# Pluvion_2_-_Rev_G.net
KiCad netlist of a schematic drawn in EAGLE
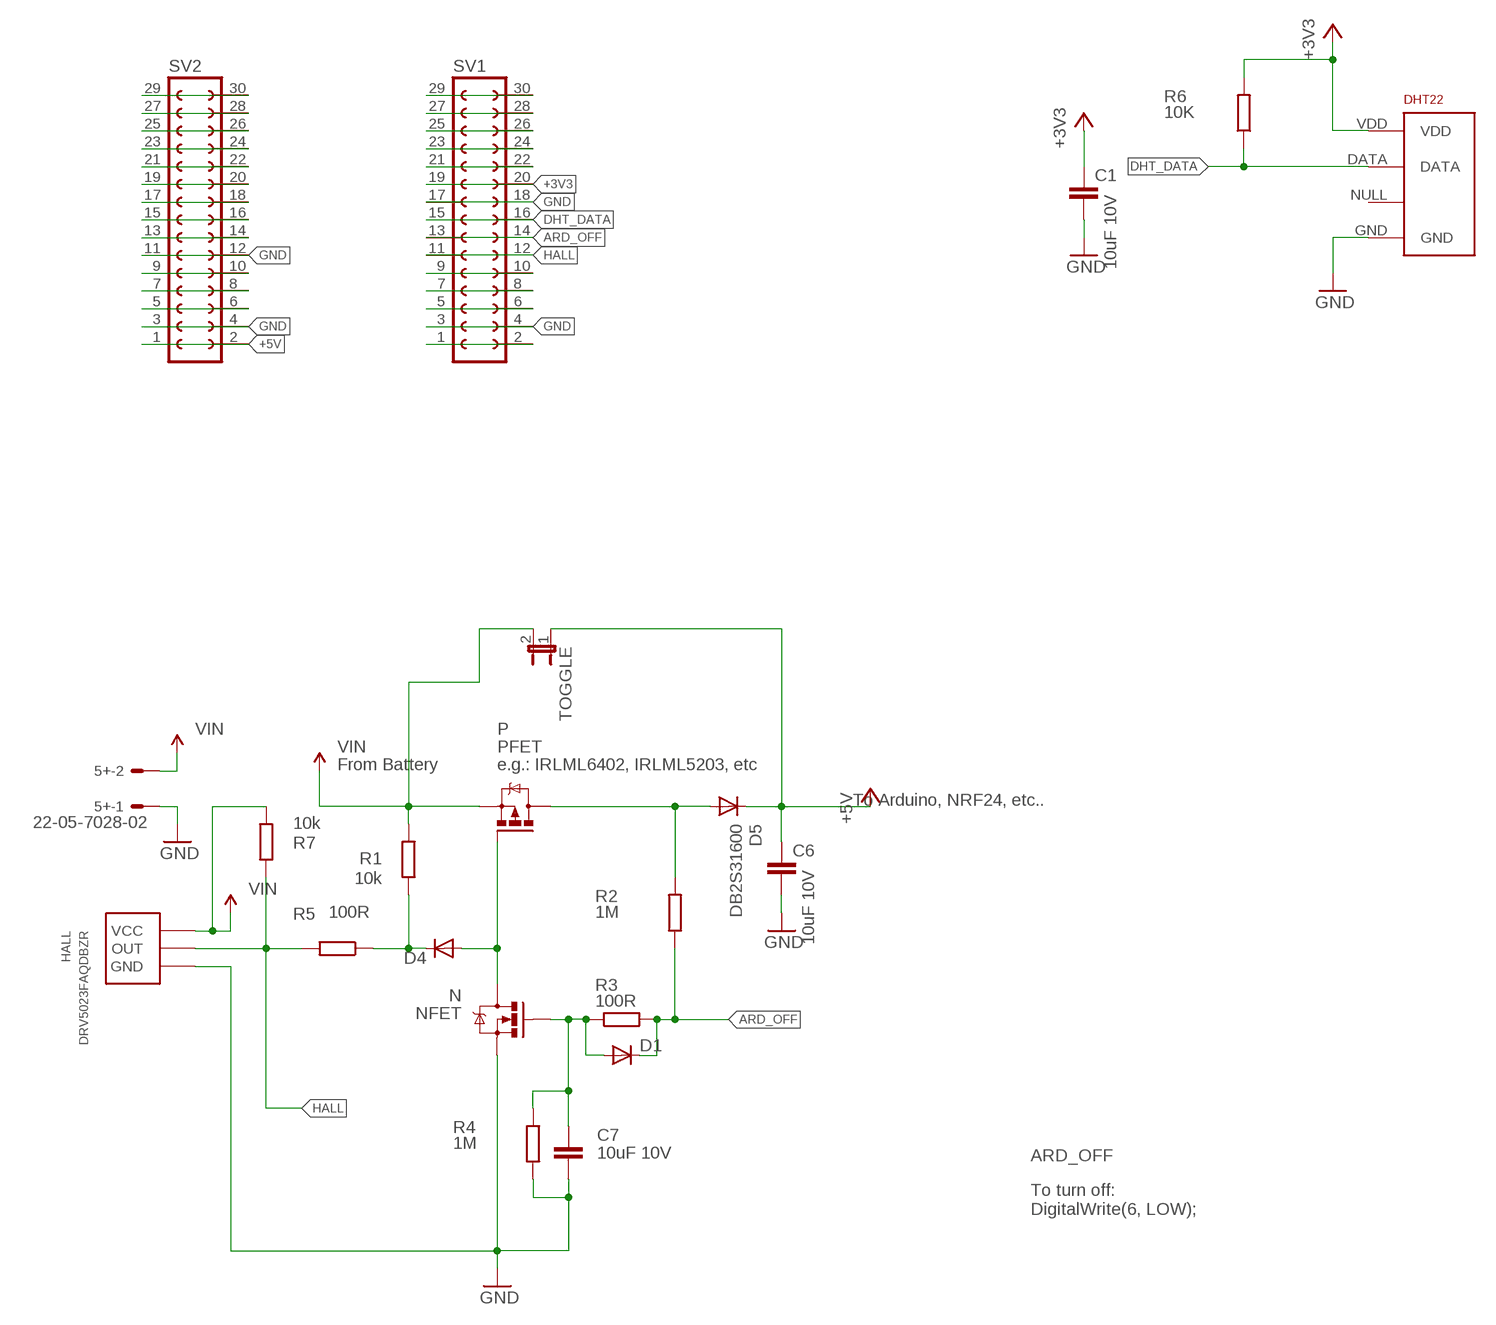
[diagram p0: schematic, sheet 1]

(export (version "E")
  (design (tool "Eeschema 10.0.6"))
  (components
    (comp (ref "5+")
      (value "22-05-7028-02")
      (footprint "eagle-import:7395-02")
      (libsource (lib "eagle-import") (part "22-?-0205-7028"))
    )
    (comp (ref "C1")
      (value "10uF 10V")
      (footprint "eagle-import:C0805")
      (libsource (lib "eagle-import") (part "C-EUC0805"))
    )
    (comp (ref "C6")
      (value "10uF 10V")
      (footprint "eagle-import:C0805")
      (libsource (lib "eagle-import") (part "C-EUC0805"))
    )
    (comp (ref "C7")
      (value "10uF 10V")
      (footprint "eagle-import:C0805")
      (libsource (lib "eagle-import") (part "C-EUC0805"))
    )
    (comp (ref "D1")
      (value "DIODESOD")
      (footprint "eagle-import:SOD-323")
      (libsource (lib "eagle-import") (part "DIODESOD"))
    )
    (comp (ref "D4")
      (value "DIODESOD")
      (footprint "eagle-import:SOD-323")
      (libsource (lib "eagle-import") (part "DIODESOD"))
    )
    (comp (ref "D5")
      (value "DB2S31600")
      (footprint "eagle-import:SMA-DIODE")
      (libsource (lib "eagle-import") (part "DIODESMA"))
    )
    (comp (ref "DHT22")
      (value "RHT03_DHT-22_AM2302RA")
      (footprint "eagle-import:RHT03_DHT-22_RA")
      (libsource (lib "eagle-import") (part "RHT03_DHT-22_AM2302RA"))
    )
    (comp (ref "HALL")
      (value "DRV5023FAQDBZR")
      (footprint "eagle-import:SOT23")
      (libsource (lib "eagle-import") (part "DRV5023FAQDBZR"))
    )
    (comp (ref "N")
      (value "NFET")
      (footprint "eagle-import:SOT23")
      (libsource (lib "eagle-import") (part "MOSFET-NCHANNELBSS123LT1G"))
    )
    (comp (ref "P")
      (value "PFET")
      (footprint "eagle-import:MICRO3")
      (libsource (lib "eagle-import") (part "IRLML5203"))
    )
    (comp (ref "R1")
      (value "10k")
      (footprint "eagle-import:R0805")
      (libsource (lib "eagle-import") (part "R-EU_R0805"))
    )
    (comp (ref "R2")
      (value "1M")
      (footprint "eagle-import:R0805")
      (libsource (lib "eagle-import") (part "R-EU_R0805"))
    )
    (comp (ref "R3")
      (value "100R")
      (footprint "eagle-import:R0805")
      (libsource (lib "eagle-import") (part "R-EU_R0805"))
    )
    (comp (ref "R4")
      (value "1M")
      (footprint "eagle-import:R0805")
      (libsource (lib "eagle-import") (part "R-EU_R0805"))
    )
    (comp (ref "R5")
      (value "100R")
      (footprint "eagle-import:R0805")
      (libsource (lib "eagle-import") (part "R-EU_R0805"))
    )
    (comp (ref "R6")
      (value "10K")
      (footprint "eagle-import:R0805")
      (libsource (lib "eagle-import") (part "R-EU_R0805"))
    )
    (comp (ref "R7")
      (value "10k")
      (footprint "eagle-import:R0805")
      (libsource (lib "eagle-import") (part "R-EU_R0805"))
    )
    (comp (ref "SV1")
      (value "FE15-2")
      (footprint "eagle-import:FE15-2")
      (libsource (lib "eagle-import") (part "FE15-2"))
    )
    (comp (ref "SV2")
      (value "FE15-2")
      (footprint "eagle-import:FE15-2")
      (libsource (lib "eagle-import") (part "FE15-2"))
    )
    (comp (ref "TOGGLE")
      (value "JUMPER-2PTH")
      (footprint "eagle-import:1X02")
      (libsource (lib "eagle-import") (part "JUMPER-2PTH"))
    )
  )
  (nets
    (net (code "1") (name "+3V3") (class "Default")
      (node (ref "C1") (pin "1") (pinfunction "1_1") (pintype "passive"))
      (node (ref "DHT22") (pin "VDD") (pinfunction "VDD_VDD") (pintype "power_in"))
      (node (ref "R6") (pin "2") (pinfunction "2_2") (pintype "passive"))
      (node (ref "SV1") (pin "19") (pinfunction "19_19") (pintype "passive"))
      (node (ref "SV1") (pin "20") (pinfunction "20_20") (pintype "passive"))
    )
    (net (code "2") (name "+5V") (class "Default")
      (node (ref "C6") (pin "1") (pinfunction "1_1") (pintype "passive"))
      (node (ref "D5") (pin "C") (pinfunction "C_C") (pintype "passive"))
      (node (ref "SV2") (pin "1") (pinfunction "1_1") (pintype "passive"))
      (node (ref "SV2") (pin "2") (pinfunction "2_2") (pintype "passive"))
      (node (ref "TOGGLE") (pin "1") (pinfunction "1_1") (pintype "passive"))
    )
    (net (code "3") (name "ARD_OFF") (class "Default")
      (node (ref "D1") (pin "1") (pinfunction "C_1") (pintype "passive"))
      (node (ref "R2") (pin "1") (pinfunction "1_1") (pintype "passive"))
      (node (ref "R3") (pin "2") (pinfunction "2_2") (pintype "passive"))
      (node (ref "SV1") (pin "13") (pinfunction "13_13") (pintype "passive"))
      (node (ref "SV1") (pin "14") (pinfunction "14_14") (pintype "passive"))
    )
    (net (code "4") (name "DHT_DATA") (class "Default")
      (node (ref "DHT22") (pin "DATA") (pinfunction "DATA_DATA") (pintype "bidirectional"))
      (node (ref "R6") (pin "1") (pinfunction "1_1") (pintype "passive"))
      (node (ref "SV1") (pin "15") (pinfunction "15_15") (pintype "passive"))
      (node (ref "SV1") (pin "16") (pinfunction "16_16") (pintype "passive"))
    )
    (net (code "5") (name "GND") (class "Default")
      (node (ref "5+") (pin "1") (pinfunction "S_1") (pintype "passive"))
      (node (ref "C1") (pin "2") (pinfunction "2_2") (pintype "passive"))
      (node (ref "C6") (pin "2") (pinfunction "2_2") (pintype "passive"))
      (node (ref "C7") (pin "2") (pinfunction "2_2") (pintype "passive"))
      (node (ref "DHT22") (pin "GND") (pinfunction "GND_GND") (pintype "power_in"))
      (node (ref "HALL") (pin "3") (pinfunction "GND_3") (pintype "bidirectional"))
      (node (ref "N") (pin "2") (pinfunction "S_2") (pintype "passive"))
      (node (ref "R4") (pin "1") (pinfunction "1_1") (pintype "passive"))
      (node (ref "SV1") (pin "17") (pinfunction "17_17") (pintype "passive"))
      (node (ref "SV1") (pin "18") (pinfunction "18_18") (pintype "passive"))
      (node (ref "SV1") (pin "3") (pinfunction "3_3") (pintype "passive"))
      (node (ref "SV1") (pin "4") (pinfunction "4_4") (pintype "passive"))
      (node (ref "SV2") (pin "11") (pinfunction "11_11") (pintype "passive"))
      (node (ref "SV2") (pin "12") (pinfunction "12_12") (pintype "passive"))
      (node (ref "SV2") (pin "3") (pinfunction "3_3") (pintype "passive"))
      (node (ref "SV2") (pin "4") (pinfunction "4_4") (pintype "passive"))
    )
    (net (code "6") (name "HALL") (class "Default")
      (node (ref "HALL") (pin "2") (pinfunction "OUT_2") (pintype "bidirectional"))
      (node (ref "R5") (pin "2") (pinfunction "2_2") (pintype "passive"))
      (node (ref "R7") (pin "2") (pinfunction "2_2") (pintype "passive"))
      (node (ref "SV1") (pin "11") (pinfunction "11_11") (pintype "passive"))
      (node (ref "SV1") (pin "12") (pinfunction "12_12") (pintype "passive"))
    )
    (net (code "7") (name "Net-(D1-A)") (class "Default")
      (node (ref "C7") (pin "1") (pinfunction "1_1") (pintype "passive"))
      (node (ref "D1") (pin "2") (pinfunction "A_2") (pintype "passive"))
      (node (ref "N") (pin "1") (pinfunction "G_1") (pintype "passive"))
      (node (ref "R3") (pin "1") (pinfunction "1_1") (pintype "passive"))
      (node (ref "R4") (pin "2") (pinfunction "2_2") (pintype "passive"))
    )
    (net (code "8") (name "Net-(D4-A)") (class "Default")
      (node (ref "D4") (pin "2") (pinfunction "A_2") (pintype "passive"))
      (node (ref "N") (pin "3") (pinfunction "D_3") (pintype "passive"))
      (node (ref "P") (pin "1") (pinfunction "G_1") (pintype "passive"))
    )
    (net (code "9") (name "Net-(D4-C)") (class "Default")
      (node (ref "D4") (pin "1") (pinfunction "C_1") (pintype "passive"))
      (node (ref "R1") (pin "1") (pinfunction "1_1") (pintype "passive"))
      (node (ref "R5") (pin "1") (pinfunction "1_1") (pintype "passive"))
    )
    (net (code "10") (name "Net-(P-D)") (class "Default")
      (node (ref "D5") (pin "A") (pinfunction "A_A") (pintype "passive"))
      (node (ref "P") (pin "3") (pinfunction "D_3") (pintype "passive"))
      (node (ref "R2") (pin "2") (pinfunction "2_2") (pintype "passive"))
    )
    (net (code "11") (name "Net-(SV1-Pad1)") (class "Default")
      (node (ref "SV1") (pin "1") (pinfunction "1_1") (pintype "passive"))
      (node (ref "SV1") (pin "2") (pinfunction "2_2") (pintype "passive"))
    )
    (net (code "12") (name "Net-(SV1-Pad5)") (class "Default")
      (node (ref "SV1") (pin "5") (pinfunction "5_5") (pintype "passive"))
      (node (ref "SV1") (pin "6") (pinfunction "6_6") (pintype "passive"))
    )
    (net (code "13") (name "Net-(SV1-Pad7)") (class "Default")
      (node (ref "SV1") (pin "7") (pinfunction "7_7") (pintype "passive"))
      (node (ref "SV1") (pin "8") (pinfunction "8_8") (pintype "passive"))
    )
    (net (code "14") (name "Net-(SV1-Pad10)") (class "Default")
      (node (ref "SV1") (pin "10") (pinfunction "10_10") (pintype "passive"))
      (node (ref "SV1") (pin "9") (pinfunction "9_9") (pintype "passive"))
    )
    (net (code "15") (name "Net-(SV1-Pad21)") (class "Default")
      (node (ref "SV1") (pin "21") (pinfunction "21_21") (pintype "passive"))
      (node (ref "SV1") (pin "22") (pinfunction "22_22") (pintype "passive"))
    )
    (net (code "16") (name "Net-(SV1-Pad23)") (class "Default")
      (node (ref "SV1") (pin "23") (pinfunction "23_23") (pintype "passive"))
      (node (ref "SV1") (pin "24") (pinfunction "24_24") (pintype "passive"))
    )
    (net (code "17") (name "Net-(SV1-Pad25)") (class "Default")
      (node (ref "SV1") (pin "25") (pinfunction "25_25") (pintype "passive"))
      (node (ref "SV1") (pin "26") (pinfunction "26_26") (pintype "passive"))
    )
    (net (code "18") (name "Net-(SV1-Pad27)") (class "Default")
      (node (ref "SV1") (pin "27") (pinfunction "27_27") (pintype "passive"))
      (node (ref "SV1") (pin "28") (pinfunction "28_28") (pintype "passive"))
    )
    (net (code "19") (name "Net-(SV1-Pad29)") (class "Default")
      (node (ref "SV1") (pin "29") (pinfunction "29_29") (pintype "passive"))
      (node (ref "SV1") (pin "30") (pinfunction "30_30") (pintype "passive"))
    )
    (net (code "20") (name "Net-(SV2-Pad5)") (class "Default")
      (node (ref "SV2") (pin "5") (pinfunction "5_5") (pintype "passive"))
      (node (ref "SV2") (pin "6") (pinfunction "6_6") (pintype "passive"))
    )
    (net (code "21") (name "Net-(SV2-Pad7)") (class "Default")
      (node (ref "SV2") (pin "7") (pinfunction "7_7") (pintype "passive"))
      (node (ref "SV2") (pin "8") (pinfunction "8_8") (pintype "passive"))
    )
    (net (code "22") (name "Net-(SV2-Pad10)") (class "Default")
      (node (ref "SV2") (pin "10") (pinfunction "10_10") (pintype "passive"))
      (node (ref "SV2") (pin "9") (pinfunction "9_9") (pintype "passive"))
    )
    (net (code "23") (name "Net-(SV2-Pad13)") (class "Default")
      (node (ref "SV2") (pin "13") (pinfunction "13_13") (pintype "passive"))
      (node (ref "SV2") (pin "14") (pinfunction "14_14") (pintype "passive"))
    )
    (net (code "24") (name "Net-(SV2-Pad15)") (class "Default")
      (node (ref "SV2") (pin "15") (pinfunction "15_15") (pintype "passive"))
      (node (ref "SV2") (pin "16") (pinfunction "16_16") (pintype "passive"))
    )
    (net (code "25") (name "Net-(SV2-Pad17)") (class "Default")
      (node (ref "SV2") (pin "17") (pinfunction "17_17") (pintype "passive"))
      (node (ref "SV2") (pin "18") (pinfunction "18_18") (pintype "passive"))
    )
    (net (code "26") (name "Net-(SV2-Pad19)") (class "Default")
      (node (ref "SV2") (pin "19") (pinfunction "19_19") (pintype "passive"))
      (node (ref "SV2") (pin "20") (pinfunction "20_20") (pintype "passive"))
    )
    (net (code "27") (name "Net-(SV2-Pad21)") (class "Default")
      (node (ref "SV2") (pin "21") (pinfunction "21_21") (pintype "passive"))
      (node (ref "SV2") (pin "22") (pinfunction "22_22") (pintype "passive"))
    )
    (net (code "28") (name "Net-(SV2-Pad23)") (class "Default")
      (node (ref "SV2") (pin "23") (pinfunction "23_23") (pintype "passive"))
      (node (ref "SV2") (pin "24") (pinfunction "24_24") (pintype "passive"))
    )
    (net (code "29") (name "Net-(SV2-Pad25)") (class "Default")
      (node (ref "SV2") (pin "25") (pinfunction "25_25") (pintype "passive"))
      (node (ref "SV2") (pin "26") (pinfunction "26_26") (pintype "passive"))
    )
    (net (code "30") (name "Net-(SV2-Pad27)") (class "Default")
      (node (ref "SV2") (pin "27") (pinfunction "27_27") (pintype "passive"))
      (node (ref "SV2") (pin "28") (pinfunction "28_28") (pintype "passive"))
    )
    (net (code "31") (name "Net-(SV2-Pad29)") (class "Default")
      (node (ref "SV2") (pin "29") (pinfunction "29_29") (pintype "passive"))
      (node (ref "SV2") (pin "30") (pinfunction "30_30") (pintype "passive"))
    )
    (net (code "32") (name "VIN") (class "Default")
      (node (ref "5+") (pin "2") (pinfunction "S_2") (pintype "passive"))
      (node (ref "HALL") (pin "1") (pinfunction "VCC_1") (pintype "bidirectional"))
      (node (ref "P") (pin "2") (pinfunction "S_2") (pintype "passive"))
      (node (ref "R1") (pin "2") (pinfunction "2_2") (pintype "passive"))
      (node (ref "R7") (pin "1") (pinfunction "1_1") (pintype "passive"))
      (node (ref "TOGGLE") (pin "2") (pinfunction "2_2") (pintype "passive"))
    )
    (net (code "33") (name "unconnected-(DHT22-PadNULL)") (class "Default")
      (node (ref "DHT22") (pin "NULL") (pinfunction "NULL_NULL") (pintype "no_connect"))
    )
  )
)
